# RC_Car_Project_Remote.net
KiCad netlist of a schematic drawn in EasyEDA
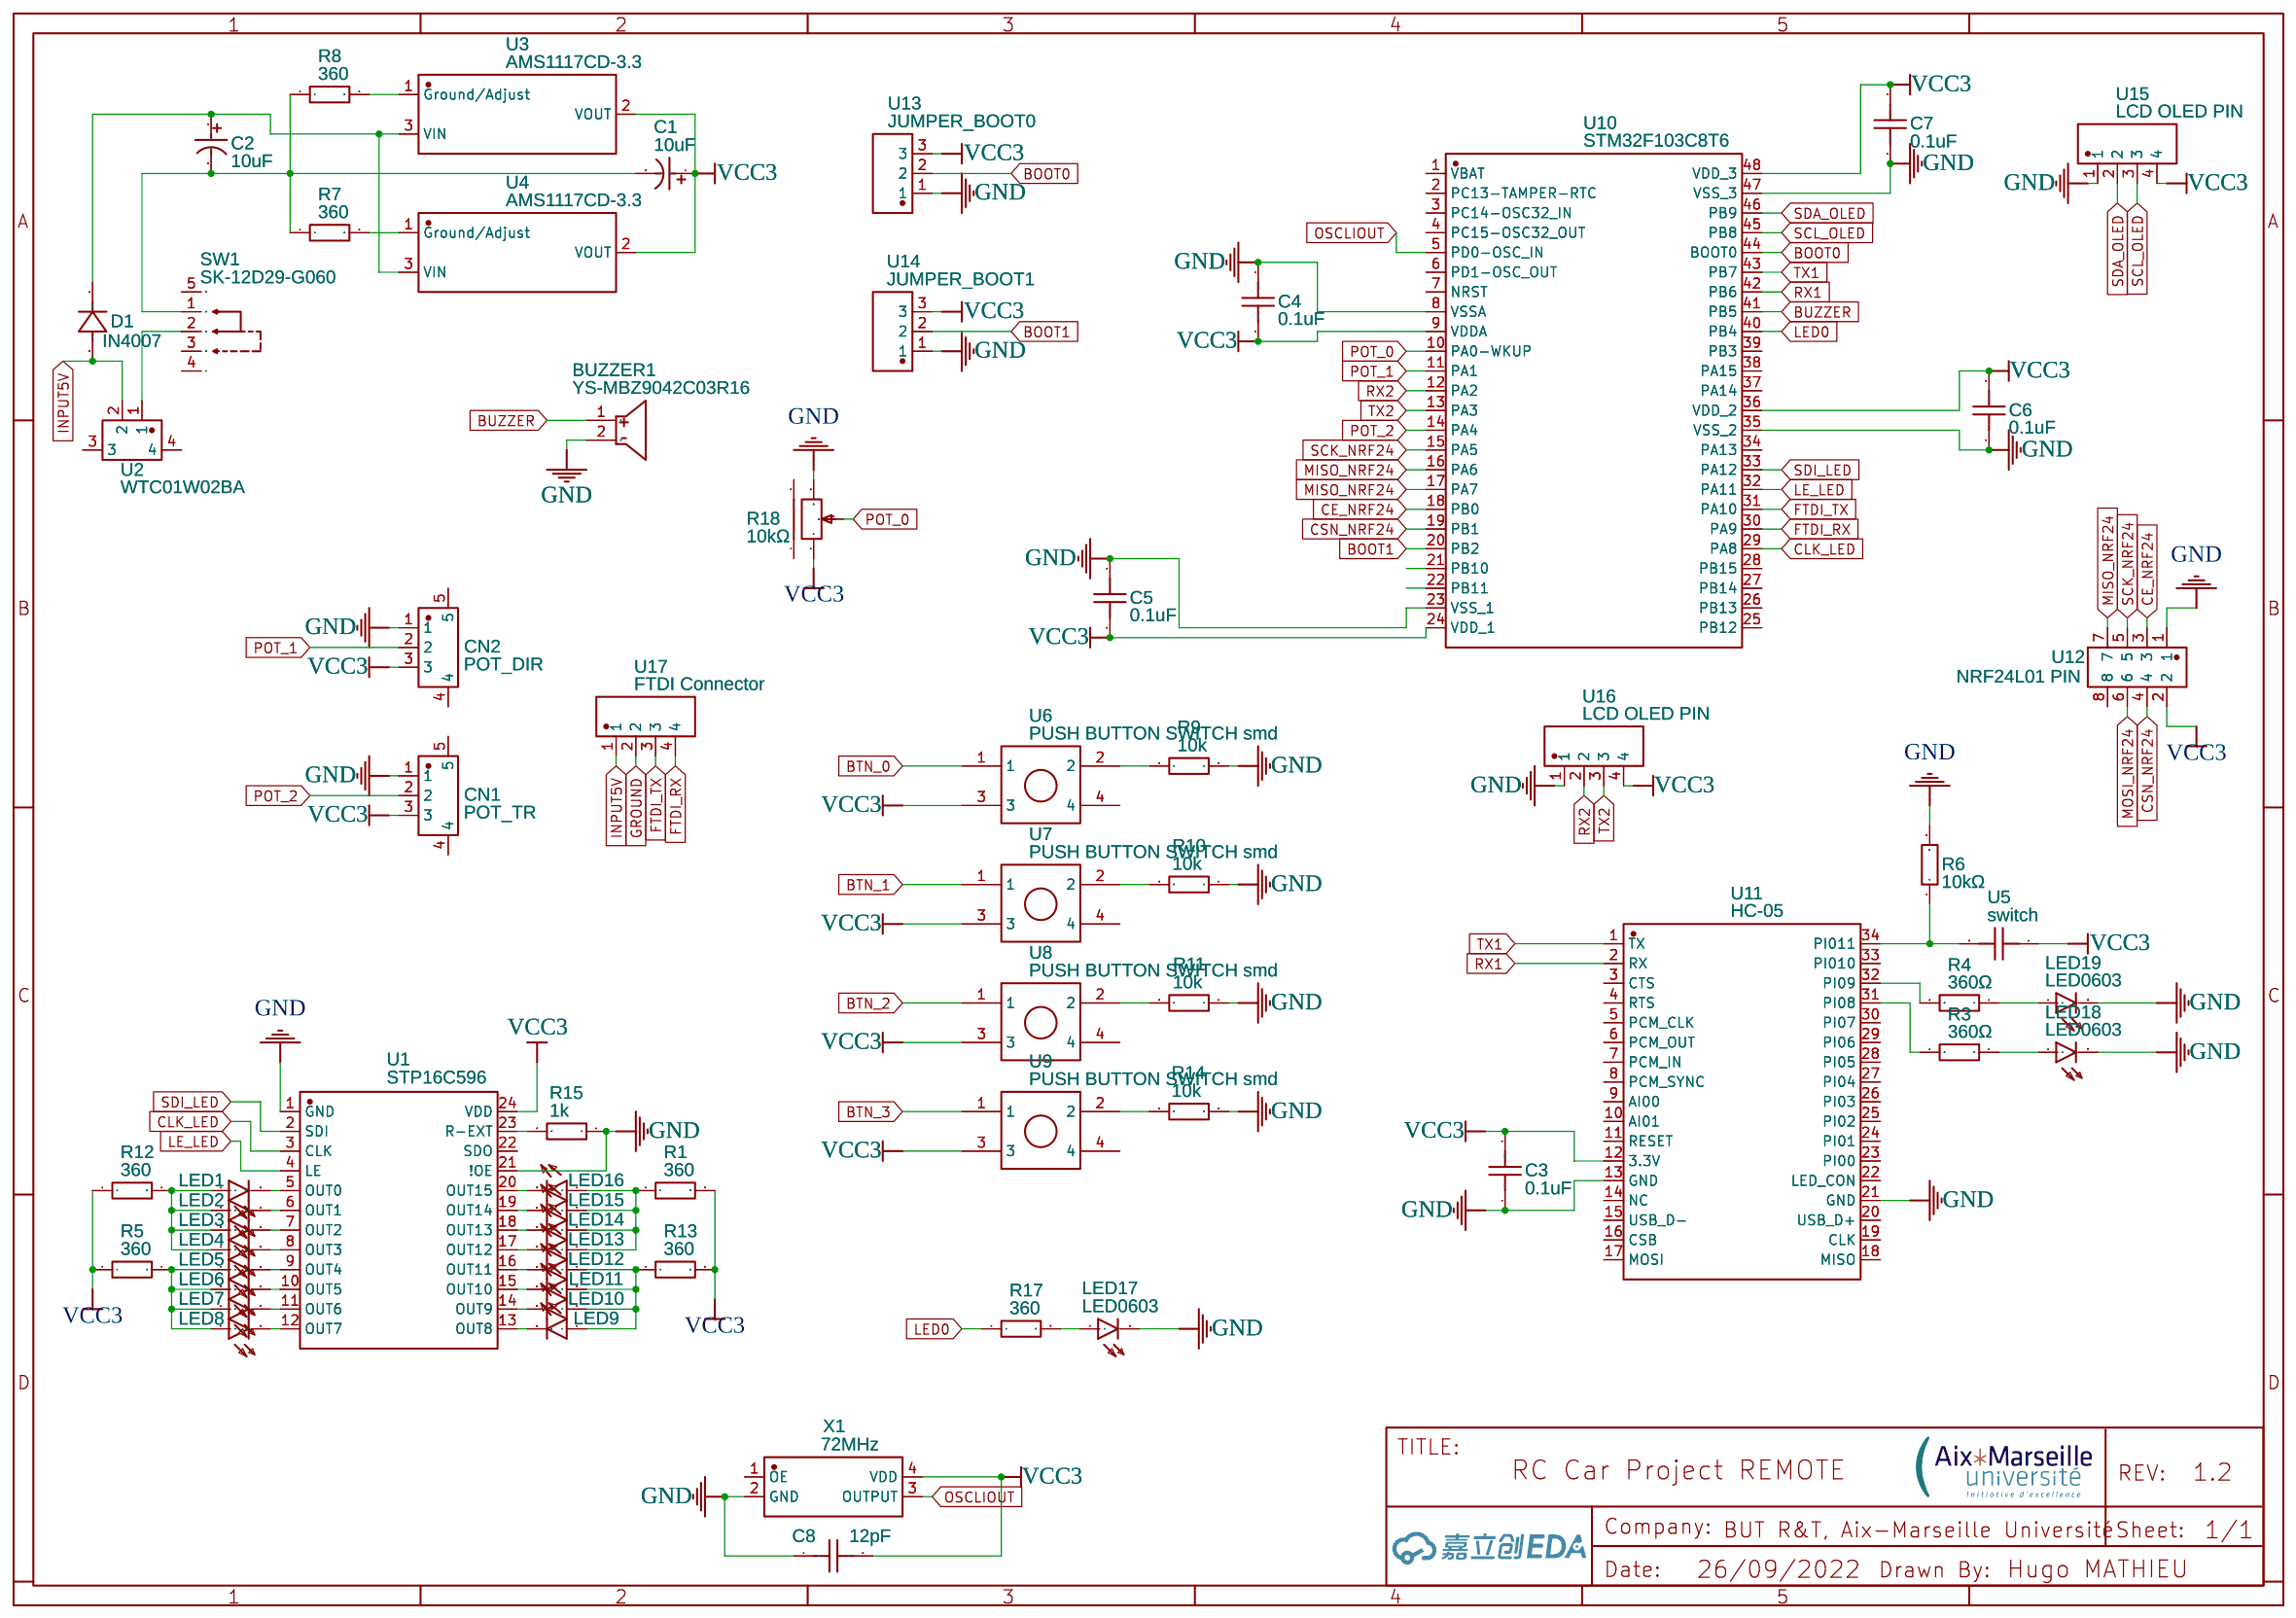
[diagram p0: schematic sheet]

(export (version "E")
  (design (tool "Eeschema 10.0.6"))
  (components
    (comp (ref "BUZZER1")
      (value "YS-MBZ9042C03R16")
      (fields (field (name "BOM_Supplier Part") "C409836"))
      (libsource (lib "") (part "YS-MBZ9042C03R16"))
    )
    (comp (ref "C1")
      (value "10uF")
      (fields
        (field (name "BOM_Manufacturer Part") "RVT1H100M0505")
        (field (name "BOM_Supplier Part") "C72487")
      )
      (libsource (lib "") (part "RVT1H100M0505"))
    )
    (comp (ref "C2")
      (value "10uF")
      (fields
        (field (name "BOM_Manufacturer Part") "RVT1H100M0505")
        (field (name "BOM_Supplier Part") "C72487")
      )
      (libsource (lib "") (part "RVT1H100M0505_1"))
    )
    (comp (ref "C3")
      (value "0.1uF")
      (fields
        (field (name "BOM_Manufacturer Part") "AC0805JRNPO9BN220")
        (field (name "BOM_Supplier Part") "C149614")
      )
      (libsource (lib "") (part "AC0805JRNPO9BN220_1"))
    )
    (comp (ref "C4")
      (value "0.1uF")
      (fields
        (field (name "BOM_Manufacturer Part") "AC0805JRNPO9BN220")
        (field (name "BOM_Supplier Part") "C149614")
      )
      (libsource (lib "") (part "AC0805JRNPO9BN220_2"))
    )
    (comp (ref "C5")
      (value "0.1uF")
      (fields
        (field (name "BOM_Manufacturer Part") "AC0805JRNPO9BN220")
        (field (name "BOM_Supplier Part") "C149614")
      )
      (libsource (lib "") (part "AC0805JRNPO9BN220_2"))
    )
    (comp (ref "C6")
      (value "0.1uF")
      (fields
        (field (name "BOM_Manufacturer Part") "AC0805JRNPO9BN220")
        (field (name "BOM_Supplier Part") "C149614")
      )
      (libsource (lib "") (part "AC0805JRNPO9BN220_1"))
    )
    (comp (ref "C7")
      (value "0.1uF")
      (fields
        (field (name "BOM_Manufacturer Part") "AC0805JRNPO9BN220")
        (field (name "BOM_Supplier Part") "C149614")
      )
      (libsource (lib "") (part "AC0805JRNPO9BN220_1"))
    )
    (comp (ref "C8")
      (value "12pF")
      (fields
        (field (name "BOM_Manufacturer Part") "AC0805JRNPO9BN220")
        (field (name "BOM_Supplier Part") "C149614")
      )
      (libsource (lib "") (part "AC0805JRNPO9BN220"))
    )
    (comp (ref "CN1")
      (value "POT_TR")
      (fields (field (name "BOM_Manufacturer Part") "1.25T-3PWT") (field (name "BOM_Supplier Part") "C22075"))
      (libsource (lib "") (part "1.25T-3PWT"))
    )
    (comp (ref "CN2")
      (value "POT_DIR")
      (fields (field (name "BOM_Manufacturer Part") "1.25T-3PWT") (field (name "BOM_Supplier Part") "C22075"))
      (libsource (lib "") (part "1.25T-3PWT"))
    )
    (comp (ref "D1")
      (value "IN4007")
      (fields (field (name "BOM_Supplier Part") "C9900004719"))
      (libsource (lib "") (part "IN4007"))
    )
    (comp (ref "LED1") (value "LED0603") (libsource (lib "") (part "LED_LEDCHIP-LED0603")))
    (comp (ref "LED2") (value "LED0603") (libsource (lib "") (part "LED_LEDCHIP-LED0603")))
    (comp (ref "LED3") (value "LED0603") (libsource (lib "") (part "LED_LEDCHIP-LED0603")))
    (comp (ref "LED4") (value "LED0603") (libsource (lib "") (part "LED_LEDCHIP-LED0603")))
    (comp (ref "LED5") (value "LED0603") (libsource (lib "") (part "LED_LEDCHIP-LED0603")))
    (comp (ref "LED6") (value "LED0603") (libsource (lib "") (part "LED_LEDCHIP-LED0603")))
    (comp (ref "LED7") (value "LED0603") (libsource (lib "") (part "LED_LEDCHIP-LED0603")))
    (comp (ref "LED8") (value "LED0603") (libsource (lib "") (part "LED_LEDCHIP-LED0603")))
    (comp (ref "LED9") (value "LED0603") (libsource (lib "") (part "LED_LEDCHIP-LED0603_1")))
    (comp (ref "LED10") (value "LED0603") (libsource (lib "") (part "LED_LEDCHIP-LED0603_1")))
    (comp (ref "LED11") (value "LED0603") (libsource (lib "") (part "LED_LEDCHIP-LED0603_1")))
    (comp (ref "LED12") (value "LED0603") (libsource (lib "") (part "LED_LEDCHIP-LED0603_1")))
    (comp (ref "LED13") (value "LED0603") (libsource (lib "") (part "LED_LEDCHIP-LED0603_1")))
    (comp (ref "LED14") (value "LED0603") (libsource (lib "") (part "LED_LEDCHIP-LED0603_1")))
    (comp (ref "LED15") (value "LED0603") (libsource (lib "") (part "LED_LEDCHIP-LED0603_1")))
    (comp (ref "LED16") (value "LED0603") (libsource (lib "") (part "LED_LEDCHIP-LED0603_1")))
    (comp (ref "LED17") (value "LED0603") (libsource (lib "") (part "LED_LEDCHIP-LED0603")))
    (comp (ref "LED18") (value "LED0603") (libsource (lib "") (part "LED_LEDCHIP-LED0603")))
    (comp (ref "LED19") (value "LED0603") (libsource (lib "") (part "LED_LEDCHIP-LED0603")))
    (comp (ref "R1")
      (value "360")
      (fields
        (field (name "BOM_Manufacturer Part") "RC0805FR-07100RL")
        (field (name "BOM_Supplier Part") "C105577")
      )
      (libsource (lib "") (part "RC0805FR-07100RL"))
    )
    (comp (ref "R3")
      (value "360Ω")
      (fields
        (field (name "BOM_Manufacturer Part") "1206W4F1002T5E")
        (field (name "BOM_Supplier Part") "C17902")
      )
      (libsource (lib "") (part "1206W4F1002T5E"))
    )
    (comp (ref "R4")
      (value "360Ω")
      (fields
        (field (name "BOM_Manufacturer Part") "1206W4F1002T5E")
        (field (name "BOM_Supplier Part") "C17902")
      )
      (libsource (lib "") (part "1206W4F1002T5E"))
    )
    (comp (ref "R5")
      (value "360")
      (fields
        (field (name "BOM_Manufacturer Part") "RC0805FR-07100RL")
        (field (name "BOM_Supplier Part") "C105577")
      )
      (libsource (lib "") (part "RC0805FR-07100RL"))
    )
    (comp (ref "R6")
      (value "10kΩ")
      (fields
        (field (name "BOM_Manufacturer Part") "1206W4F1002T5E")
        (field (name "BOM_Supplier Part") "C17902")
      )
      (libsource (lib "") (part "1206W4F1002T5E_1"))
    )
    (comp (ref "R7")
      (value "360")
      (fields
        (field (name "BOM_Manufacturer Part") "RC0805FR-07100RL")
        (field (name "BOM_Supplier Part") "C105577")
      )
      (libsource (lib "") (part "RC0805FR-07100RL"))
    )
    (comp (ref "R8")
      (value "360")
      (fields
        (field (name "BOM_Manufacturer Part") "RC0805FR-07100RL")
        (field (name "BOM_Supplier Part") "C105577")
      )
      (libsource (lib "") (part "RC0805FR-07100RL"))
    )
    (comp (ref "R9")
      (value "10k")
      (fields
        (field (name "BOM_Manufacturer Part") "RC0805FR-07100RL")
        (field (name "BOM_Supplier Part") "C105577")
      )
      (libsource (lib "") (part "RC0805FR-07100RL_1"))
    )
    (comp (ref "R10")
      (value "10k")
      (fields
        (field (name "BOM_Manufacturer Part") "RC0805FR-07100RL")
        (field (name "BOM_Supplier Part") "C105577")
      )
      (libsource (lib "") (part "RC0805FR-07100RL_1"))
    )
    (comp (ref "R11")
      (value "10k")
      (fields
        (field (name "BOM_Manufacturer Part") "RC0805FR-07100RL")
        (field (name "BOM_Supplier Part") "C105577")
      )
      (libsource (lib "") (part "RC0805FR-07100RL_1"))
    )
    (comp (ref "R12")
      (value "360")
      (fields
        (field (name "BOM_Manufacturer Part") "RC0805FR-07100RL")
        (field (name "BOM_Supplier Part") "C105577")
      )
      (libsource (lib "") (part "RC0805FR-07100RL"))
    )
    (comp (ref "R13")
      (value "360")
      (fields
        (field (name "BOM_Manufacturer Part") "RC0805FR-07100RL")
        (field (name "BOM_Supplier Part") "C105577")
      )
      (libsource (lib "") (part "RC0805FR-07100RL"))
    )
    (comp (ref "R14")
      (value "10k")
      (fields
        (field (name "BOM_Manufacturer Part") "RC0805FR-07100RL")
        (field (name "BOM_Supplier Part") "C105577")
      )
      (libsource (lib "") (part "RC0805FR-07100RL_1"))
    )
    (comp (ref "R15")
      (value "1k")
      (fields
        (field (name "BOM_Manufacturer Part") "RC0805FR-07100RL")
        (field (name "BOM_Supplier Part") "C105577")
      )
      (libsource (lib "") (part "RC0805FR-07100RL_1"))
    )
    (comp (ref "R17")
      (value "360")
      (fields
        (field (name "BOM_Manufacturer Part") "RC0805FR-07100RL")
        (field (name "BOM_Supplier Part") "C105577")
      )
      (libsource (lib "") (part "RC0805FR-07100RL"))
    )
    (comp (ref "R18")
      (value "10kΩ")
      (fields
        (field (name "BOM_Manufacturer Part") "RK09K1130AP5")
        (field (name "BOM_Supplier Part") "C470295")
      )
      (libsource (lib "") (part "RK09K1130AP5"))
    )
    (comp (ref "SW1")
      (value "SK-12D29-G060")
      (fields (field (name "BOM_Supplier Part") "C2848877"))
      (libsource (lib "") (part "SK-12D29-G060"))
    )
    (comp (ref "U1")
      (value "STP16C596")
      (fields (field (name "BOM_Supplier Part") "914-2948"))
      (libsource (lib "") (part "STP16C596"))
    )
    (comp (ref "U2")
      (value "WTC01W02BA")
      (fields (field (name "BOM_Supplier Part") "C5120226"))
      (libsource (lib "") (part "WTC01W02BA"))
    )
    (comp (ref "U3")
      (value "AMS1117CD-3.3")
      (fields (field (name "BOM_Supplier Part") "C841796"))
      (libsource (lib "") (part "AMS1117CD-3.3"))
    )
    (comp (ref "U4")
      (value "AMS1117CD-3.3")
      (fields (field (name "BOM_Supplier Part") "C841796"))
      (libsource (lib "") (part "AMS1117CD-3.3"))
    )
    (comp (ref "U5")
      (value "switch")
      (fields
        (field (name "BOM_Manufacturer Part") "0.5pF-C0805")
        (field (name "BOM_Supplier Part") "C9900009443")
      )
      (libsource (lib "") (part "0.5PF-C0805"))
    )
    (comp (ref "U6")
      (value "PUSH BUTTON SWITCH smd")
      (fields (field (name "BOM_Manufacturer Part") "HALO PUSH BUTTON SWITCH"))
      (libsource (lib "") (part "PUSH BUTTON SWITCH smd"))
    )
    (comp (ref "U7")
      (value "PUSH BUTTON SWITCH smd")
      (fields (field (name "BOM_Manufacturer Part") "HALO PUSH BUTTON SWITCH"))
      (libsource (lib "") (part "PUSH BUTTON SWITCH smd"))
    )
    (comp (ref "U8")
      (value "PUSH BUTTON SWITCH smd")
      (fields (field (name "BOM_Manufacturer Part") "HALO PUSH BUTTON SWITCH"))
      (libsource (lib "") (part "PUSH BUTTON SWITCH smd"))
    )
    (comp (ref "U9")
      (value "PUSH BUTTON SWITCH smd")
      (fields (field (name "BOM_Manufacturer Part") "HALO PUSH BUTTON SWITCH"))
      (libsource (lib "") (part "PUSH BUTTON SWITCH smd"))
    )
    (comp (ref "U10")
      (value "STM32F103C8T6")
      (fields (field (name "BOM_Supplier Part") "C8734"))
      (libsource (lib "") (part "STM32F103C8T6"))
    )
    (comp (ref "U11")
      (value "HC-05")
      (fields (field (name "BOM_Supplier Part") "C9900001063"))
      (libsource (lib "") (part "HC-05"))
    )
    (comp (ref "U12")
      (value "NRF24L01 PIN")
      (fields (field (name "BOM_Manufacturer Part") "2.54-2*4") (field (name "BOM_Supplier Part") "C2977588"))
      (libsource (lib "") (part "2.54-2*4"))
    )
    (comp (ref "U13")
      (value "JUMPER_BOOT0")
      (fields
        (field (name "BOM_Manufacturer Part") "2.54*3单排")
        (field (name "BOM_Supplier Part") "C9900016162")
      )
      (libsource (lib "") (part "2.54*3单排"))
    )
    (comp (ref "U14")
      (value "JUMPER_BOOT1")
      (fields
        (field (name "BOM_Manufacturer Part") "2.54*3单排")
        (field (name "BOM_Supplier Part") "C9900016162")
      )
      (libsource (lib "") (part "2.54*3单排"))
    )
    (comp (ref "U15")
      (value "LCD OLED PIN")
      (fields
        (field (name "BOM_Manufacturer Part") "2.54*4单排")
        (field (name "BOM_Supplier Part") "C9900016163")
      )
      (libsource (lib "") (part "2.54*4单排"))
    )
    (comp (ref "U16")
      (value "LCD OLED PIN")
      (fields
        (field (name "BOM_Manufacturer Part") "2.54*4单排")
        (field (name "BOM_Supplier Part") "C9900016163")
      )
      (libsource (lib "") (part "2.54*4单排"))
    )
    (comp (ref "U17")
      (value "FTDI Connector")
      (fields
        (field (name "BOM_Manufacturer Part") "2.54*4单排")
        (field (name "BOM_Supplier Part") "C9900016163")
      )
      (libsource (lib "") (part "2.54*4单排"))
    )
    (comp (ref "X1")
      (value "72MHz")
      (fields
        (field (name "BOM_Manufacturer Part") "S5D13.560000A20F30T")
        (field (name "BOM_Supplier Part") "C387226")
      )
      (libsource (lib "") (part "S5D13.560000A20F30T"))
    )
  )
  (nets
    (net (code "1") (name "BOOT0") (class "Default")
      (node (ref "U10") (pin "44") (pinfunction "BOOT0_44") (pintype "unspecified"))
      (node (ref "U13") (pin "2") (pinfunction "2_2") (pintype "unspecified"))
    )
    (net (code "2") (name "BOOT1") (class "Default")
      (node (ref "U10") (pin "20") (pinfunction "PB2_20") (pintype "unspecified"))
      (node (ref "U14") (pin "2") (pinfunction "2_2") (pintype "unspecified"))
    )
    (net (code "3") (name "BTN_0") (class "Default")
      (node (ref "U6") (pin "1") (pinfunction "1_1") (pintype "unspecified"))
    )
    (net (code "4") (name "BTN_1") (class "Default")
      (node (ref "U7") (pin "1") (pinfunction "1_1") (pintype "unspecified"))
    )
    (net (code "5") (name "BTN_2") (class "Default")
      (node (ref "U8") (pin "1") (pinfunction "1_1") (pintype "unspecified"))
    )
    (net (code "6") (name "BTN_3") (class "Default")
      (node (ref "U9") (pin "1") (pinfunction "1_1") (pintype "unspecified"))
    )
    (net (code "7") (name "BUZZER") (class "Default")
      (node (ref "BUZZER1") (pin "1") (pinfunction "1_1") (pintype "unspecified"))
      (node (ref "U10") (pin "41") (pinfunction "PB5_41") (pintype "unspecified"))
    )
    (net (code "8") (name "CE_NRF24") (class "Default")
      (node (ref "U10") (pin "18") (pinfunction "PB0_18") (pintype "unspecified"))
      (node (ref "U12") (pin "3") (pinfunction "3_3") (pintype "unspecified"))
    )
    (net (code "9") (name "CLK_LED") (class "Default")
      (node (ref "U1") (pin "3") (pinfunction "CLK_3") (pintype "unspecified"))
      (node (ref "U10") (pin "29") (pinfunction "PA8_29") (pintype "unspecified"))
    )
    (net (code "10") (name "CSN_NRF24") (class "Default")
      (node (ref "U10") (pin "19") (pinfunction "PB1_19") (pintype "unspecified"))
      (node (ref "U12") (pin "4") (pinfunction "4_4") (pintype "unspecified"))
    )
    (net (code "11") (name "FTDI_RX") (class "Default")
      (node (ref "U10") (pin "30") (pinfunction "PA9_30") (pintype "unspecified"))
      (node (ref "U17") (pin "4") (pinfunction "4_4") (pintype "unspecified"))
    )
    (net (code "12") (name "FTDI_TX") (class "Default")
      (node (ref "U10") (pin "31") (pinfunction "PA10_31") (pintype "unspecified"))
      (node (ref "U17") (pin "3") (pinfunction "3_3") (pintype "unspecified"))
    )
    (net (code "13") (name "GND") (class "Default")
      (node (ref "BUZZER1") (pin "2") (pinfunction "2_2") (pintype "unspecified"))
      (node (ref "C3") (pin "1") (pinfunction "1_1") (pintype "unspecified"))
      (node (ref "C4") (pin "1") (pinfunction "1_1") (pintype "unspecified"))
      (node (ref "C5") (pin "1") (pinfunction "1_1") (pintype "unspecified"))
      (node (ref "C6") (pin "1") (pinfunction "1_1") (pintype "unspecified"))
      (node (ref "C7") (pin "1") (pinfunction "1_1") (pintype "unspecified"))
      (node (ref "C8") (pin "1") (pinfunction "1_1") (pintype "unspecified"))
      (node (ref "CN1") (pin "1") (pinfunction "1_1") (pintype "unspecified"))
      (node (ref "CN2") (pin "1") (pinfunction "1_1") (pintype "unspecified"))
      (node (ref "LED17") (pin "C") (pinfunction "C_C") (pintype "bidirectional"))
      (node (ref "LED18") (pin "C") (pinfunction "C_C") (pintype "bidirectional"))
      (node (ref "LED19") (pin "C") (pinfunction "C_C") (pintype "bidirectional"))
      (node (ref "R10") (pin "1") (pinfunction "1_1") (pintype "input"))
      (node (ref "R11") (pin "1") (pinfunction "1_1") (pintype "input"))
      (node (ref "R14") (pin "1") (pinfunction "1_1") (pintype "input"))
      (node (ref "R15") (pin "1") (pinfunction "1_1") (pintype "input"))
      (node (ref "R18") (pin "3") (pinfunction "3_3") (pintype "input"))
      (node (ref "R6") (pin "2") (pinfunction "2_2") (pintype "input"))
      (node (ref "R9") (pin "1") (pinfunction "1_1") (pintype "input"))
      (node (ref "U1") (pin "1") (pinfunction "GND_1") (pintype "unspecified"))
      (node (ref "U1") (pin "21") (pinfunction "!OE_21") (pintype "unspecified"))
      (node (ref "U10") (pin "23") (pinfunction "VSS_1_23") (pintype "unspecified"))
      (node (ref "U10") (pin "35") (pinfunction "VSS_2_35") (pintype "unspecified"))
      (node (ref "U10") (pin "47") (pinfunction "VSS_3_47") (pintype "unspecified"))
      (node (ref "U10") (pin "8") (pinfunction "VSSA_8") (pintype "unspecified"))
      (node (ref "U11") (pin "13") (pinfunction "GND_13") (pintype "unspecified"))
      (node (ref "U11") (pin "21") (pinfunction "GND_21") (pintype "unspecified"))
      (node (ref "U12") (pin "1") (pinfunction "1_1") (pintype "unspecified"))
      (node (ref "U13") (pin "1") (pinfunction "1_1") (pintype "unspecified"))
      (node (ref "U14") (pin "1") (pinfunction "1_1") (pintype "unspecified"))
      (node (ref "U15") (pin "1") (pinfunction "1_1") (pintype "unspecified"))
      (node (ref "U16") (pin "1") (pinfunction "1_1") (pintype "unspecified"))
      (node (ref "X1") (pin "2") (pinfunction "GND_2") (pintype "unspecified"))
    )
    (net (code "14") (name "GROUND") (class "Default")
      (node (ref "U17") (pin "2") (pinfunction "2_2") (pintype "unspecified"))
    )
    (net (code "15") (name "INPUT5V") (class "Default")
      (node (ref "D1") (pin "2") (pinfunction "A_2") (pintype "unspecified"))
      (node (ref "U17") (pin "1") (pinfunction "1_1") (pintype "unspecified"))
      (node (ref "U2") (pin "2") (pinfunction "2_2") (pintype "unspecified"))
    )
    (net (code "16") (name "LED0") (class "Default")
      (node (ref "R17") (pin "1") (pinfunction "1_1") (pintype "input"))
      (node (ref "U10") (pin "40") (pinfunction "PB4_40") (pintype "unspecified"))
    )
    (net (code "17") (name "LE_LED") (class "Default")
      (node (ref "U1") (pin "4") (pinfunction "LE_4") (pintype "unspecified"))
      (node (ref "U10") (pin "32") (pinfunction "PA11_32") (pintype "unspecified"))
    )
    (net (code "18") (name "MISO_NRF24") (class "Default")
      (node (ref "U10") (pin "16") (pinfunction "PA6_16") (pintype "unspecified"))
      (node (ref "U10") (pin "17") (pinfunction "PA7_17") (pintype "unspecified"))
      (node (ref "U12") (pin "7") (pinfunction "7_7") (pintype "unspecified"))
    )
    (net (code "19") (name "MOSI_NRF24") (class "Default")
      (node (ref "U12") (pin "6") (pinfunction "6_6") (pintype "unspecified"))
    )
    (net (code "20") (name "Net-(C1-Pad2)") (class "Default")
      (node (ref "C1") (pin "2") (pinfunction "2_2") (pintype "input"))
      (node (ref "C2") (pin "2") (pinfunction "2_2") (pintype "input"))
      (node (ref "R7") (pin "1") (pinfunction "1_1") (pintype "input"))
      (node (ref "R8") (pin "1") (pinfunction "1_1") (pintype "input"))
      (node (ref "SW1") (pin "1") (pinfunction "1_1") (pintype "unspecified"))
    )
    (net (code "21") (name "Net-(D1-K)") (class "Default")
      (node (ref "C2") (pin "1") (pinfunction "1_1") (pintype "input"))
      (node (ref "D1") (pin "1") (pinfunction "K_1") (pintype "unspecified"))
      (node (ref "U3") (pin "3") (pinfunction "VIN_3") (pintype "unspecified"))
      (node (ref "U4") (pin "3") (pinfunction "VIN_3") (pintype "unspecified"))
    )
    (net (code "22") (name "Net-(LED1-PadA)") (class "Default")
      (node (ref "LED1") (pin "A") (pinfunction "A_A") (pintype "bidirectional"))
      (node (ref "LED2") (pin "A") (pinfunction "A_A") (pintype "bidirectional"))
      (node (ref "LED3") (pin "A") (pinfunction "A_A") (pintype "bidirectional"))
      (node (ref "LED4") (pin "A") (pinfunction "A_A") (pintype "bidirectional"))
      (node (ref "R12") (pin "2") (pinfunction "2_2") (pintype "input"))
    )
    (net (code "23") (name "Net-(LED5-PadA)") (class "Default")
      (node (ref "LED5") (pin "A") (pinfunction "A_A") (pintype "bidirectional"))
      (node (ref "LED6") (pin "A") (pinfunction "A_A") (pintype "bidirectional"))
      (node (ref "LED7") (pin "A") (pinfunction "A_A") (pintype "bidirectional"))
      (node (ref "LED8") (pin "A") (pinfunction "A_A") (pintype "bidirectional"))
      (node (ref "R5") (pin "2") (pinfunction "2_2") (pintype "input"))
    )
    (net (code "24") (name "Net-(LED10-PadA)") (class "Default")
      (node (ref "LED10") (pin "A") (pinfunction "A_A") (pintype "bidirectional"))
      (node (ref "LED11") (pin "A") (pinfunction "A_A") (pintype "bidirectional"))
      (node (ref "LED12") (pin "A") (pinfunction "A_A") (pintype "bidirectional"))
      (node (ref "LED9") (pin "A") (pinfunction "A_A") (pintype "bidirectional"))
      (node (ref "R13") (pin "1") (pinfunction "1_1") (pintype "input"))
    )
    (net (code "25") (name "Net-(LED13-PadA)") (class "Default")
      (node (ref "LED13") (pin "A") (pinfunction "A_A") (pintype "bidirectional"))
      (node (ref "LED14") (pin "A") (pinfunction "A_A") (pintype "bidirectional"))
      (node (ref "LED15") (pin "A") (pinfunction "A_A") (pintype "bidirectional"))
      (node (ref "LED16") (pin "A") (pinfunction "A_A") (pintype "bidirectional"))
      (node (ref "R1") (pin "1") (pinfunction "1_1") (pintype "input"))
    )
    (net (code "26") (name "Net-(LED17-PadA)") (class "Default")
      (node (ref "LED17") (pin "A") (pinfunction "A_A") (pintype "bidirectional"))
      (node (ref "R17") (pin "2") (pinfunction "2_2") (pintype "input"))
    )
    (net (code "27") (name "Net-(LED18-PadA)") (class "Default")
      (node (ref "LED18") (pin "A") (pinfunction "A_A") (pintype "bidirectional"))
      (node (ref "R3") (pin "1") (pinfunction "1_1") (pintype "input"))
    )
    (net (code "28") (name "Net-(LED19-PadA)") (class "Default")
      (node (ref "LED19") (pin "A") (pinfunction "A_A") (pintype "bidirectional"))
      (node (ref "R4") (pin "1") (pinfunction "1_1") (pintype "input"))
    )
    (net (code "29") (name "Net-(R9-Pad2)") (class "Default")
      (node (ref "R9") (pin "2") (pinfunction "2_2") (pintype "input"))
      (node (ref "U6") (pin "2") (pinfunction "2_2") (pintype "unspecified"))
    )
    (net (code "30") (name "Net-(R10-Pad2)") (class "Default")
      (node (ref "R10") (pin "2") (pinfunction "2_2") (pintype "input"))
      (node (ref "U7") (pin "2") (pinfunction "2_2") (pintype "unspecified"))
    )
    (net (code "31") (name "Net-(R11-Pad2)") (class "Default")
      (node (ref "R11") (pin "2") (pinfunction "2_2") (pintype "input"))
      (node (ref "U8") (pin "2") (pinfunction "2_2") (pintype "unspecified"))
    )
    (net (code "32") (name "Net-(R14-Pad2)") (class "Default")
      (node (ref "R14") (pin "2") (pinfunction "2_2") (pintype "input"))
      (node (ref "U9") (pin "2") (pinfunction "2_2") (pintype "unspecified"))
    )
    (net (code "33") (name "Net-(SW1-Pad2)") (class "Default")
      (node (ref "SW1") (pin "2") (pinfunction "2_2") (pintype "unspecified"))
      (node (ref "U2") (pin "1") (pinfunction "1_1") (pintype "unspecified"))
    )
    (net (code "34") (name "Net-(U1-OUT0)") (class "Default")
      (node (ref "LED1") (pin "C") (pinfunction "C_C") (pintype "bidirectional"))
      (node (ref "U1") (pin "5") (pinfunction "OUT0_5") (pintype "unspecified"))
    )
    (net (code "35") (name "Net-(U1-OUT1)") (class "Default")
      (node (ref "LED2") (pin "C") (pinfunction "C_C") (pintype "bidirectional"))
      (node (ref "U1") (pin "6") (pinfunction "OUT1_6") (pintype "unspecified"))
    )
    (net (code "36") (name "Net-(U1-OUT2)") (class "Default")
      (node (ref "LED3") (pin "C") (pinfunction "C_C") (pintype "bidirectional"))
      (node (ref "U1") (pin "7") (pinfunction "OUT2_7") (pintype "unspecified"))
    )
    (net (code "37") (name "Net-(U1-OUT3)") (class "Default")
      (node (ref "LED4") (pin "C") (pinfunction "C_C") (pintype "bidirectional"))
      (node (ref "U1") (pin "8") (pinfunction "OUT3_8") (pintype "unspecified"))
    )
    (net (code "38") (name "Net-(U1-OUT4)") (class "Default")
      (node (ref "LED5") (pin "C") (pinfunction "C_C") (pintype "bidirectional"))
      (node (ref "U1") (pin "9") (pinfunction "OUT4_9") (pintype "unspecified"))
    )
    (net (code "39") (name "Net-(U1-OUT5)") (class "Default")
      (node (ref "LED6") (pin "C") (pinfunction "C_C") (pintype "bidirectional"))
      (node (ref "U1") (pin "10") (pinfunction "OUT5_10") (pintype "unspecified"))
    )
    (net (code "40") (name "Net-(U1-OUT6)") (class "Default")
      (node (ref "LED7") (pin "C") (pinfunction "C_C") (pintype "bidirectional"))
      (node (ref "U1") (pin "11") (pinfunction "OUT6_11") (pintype "unspecified"))
    )
    (net (code "41") (name "Net-(U1-OUT7)") (class "Default")
      (node (ref "LED8") (pin "C") (pinfunction "C_C") (pintype "bidirectional"))
      (node (ref "U1") (pin "12") (pinfunction "OUT7_12") (pintype "unspecified"))
    )
    (net (code "42") (name "Net-(U1-OUT8)") (class "Default")
      (node (ref "LED9") (pin "C") (pinfunction "C_C") (pintype "bidirectional"))
      (node (ref "U1") (pin "13") (pinfunction "OUT8_13") (pintype "unspecified"))
    )
    (net (code "43") (name "Net-(U1-OUT9)") (class "Default")
      (node (ref "LED10") (pin "C") (pinfunction "C_C") (pintype "bidirectional"))
      (node (ref "U1") (pin "14") (pinfunction "OUT9_14") (pintype "unspecified"))
    )
    (net (code "44") (name "Net-(U1-OUT10)") (class "Default")
      (node (ref "LED11") (pin "C") (pinfunction "C_C") (pintype "bidirectional"))
      (node (ref "U1") (pin "15") (pinfunction "OUT10_15") (pintype "unspecified"))
    )
    (net (code "45") (name "Net-(U1-OUT11)") (class "Default")
      (node (ref "LED12") (pin "C") (pinfunction "C_C") (pintype "bidirectional"))
      (node (ref "U1") (pin "16") (pinfunction "OUT11_16") (pintype "unspecified"))
    )
    (net (code "46") (name "Net-(U1-OUT12)") (class "Default")
      (node (ref "LED13") (pin "C") (pinfunction "C_C") (pintype "bidirectional"))
      (node (ref "U1") (pin "17") (pinfunction "OUT12_17") (pintype "unspecified"))
    )
    (net (code "47") (name "Net-(U1-OUT13)") (class "Default")
      (node (ref "LED14") (pin "C") (pinfunction "C_C") (pintype "bidirectional"))
      (node (ref "U1") (pin "18") (pinfunction "OUT13_18") (pintype "unspecified"))
    )
    (net (code "48") (name "Net-(U1-OUT14)") (class "Default")
      (node (ref "LED15") (pin "C") (pinfunction "C_C") (pintype "bidirectional"))
      (node (ref "U1") (pin "19") (pinfunction "OUT14_19") (pintype "unspecified"))
    )
    (net (code "49") (name "Net-(U1-OUT15)") (class "Default")
      (node (ref "LED16") (pin "C") (pinfunction "C_C") (pintype "bidirectional"))
      (node (ref "U1") (pin "20") (pinfunction "OUT15_20") (pintype "unspecified"))
    )
    (net (code "50") (name "Net-(U1-R-EXT)") (class "Default")
      (node (ref "R15") (pin "2") (pinfunction "2_2") (pintype "input"))
      (node (ref "U1") (pin "23") (pinfunction "R-EXT_23") (pintype "unspecified"))
    )
    (net (code "51") (name "Net-(U3-Ground{slash}Adjust)") (class "Default")
      (node (ref "R8") (pin "2") (pinfunction "2_2") (pintype "input"))
      (node (ref "U3") (pin "1") (pinfunction "Ground/Adjust_1") (pintype "unspecified"))
    )
    (net (code "52") (name "Net-(U4-Ground{slash}Adjust)") (class "Default")
      (node (ref "R7") (pin "2") (pinfunction "2_2") (pintype "input"))
      (node (ref "U4") (pin "1") (pinfunction "Ground/Adjust_1") (pintype "unspecified"))
    )
    (net (code "53") (name "Net-(U11-PI08)") (class "Default")
      (node (ref "R3") (pin "2") (pinfunction "2_2") (pintype "input"))
      (node (ref "U11") (pin "31") (pinfunction "PI08_31") (pintype "unspecified"))
    )
    (net (code "54") (name "Net-(U11-PI09)") (class "Default")
      (node (ref "R4") (pin "2") (pinfunction "2_2") (pintype "input"))
      (node (ref "U11") (pin "32") (pinfunction "PI09_32") (pintype "unspecified"))
    )
    (net (code "55") (name "Net-(U11-PI011)") (class "Default")
      (node (ref "R6") (pin "1") (pinfunction "1_1") (pintype "input"))
      (node (ref "U11") (pin "34") (pinfunction "PI011_34") (pintype "unspecified"))
      (node (ref "U5") (pin "2") (pinfunction "2_2") (pintype "unspecified"))
    )
    (net (code "56") (name "OSCLIOUT") (class "Default")
      (node (ref "U10") (pin "5") (pinfunction "PD0-OSC_IN_5") (pintype "unspecified"))
      (node (ref "X1") (pin "3") (pinfunction "OUTPUT_3") (pintype "unspecified"))
    )
    (net (code "57") (name "POT_0") (class "Default")
      (node (ref "R18") (pin "2") (pinfunction "2_2") (pintype "input"))
      (node (ref "U10") (pin "10") (pinfunction "PA0-WKUP_10") (pintype "unspecified"))
    )
    (net (code "58") (name "POT_1") (class "Default")
      (node (ref "CN2") (pin "2") (pinfunction "2_2") (pintype "unspecified"))
      (node (ref "U10") (pin "11") (pinfunction "PA1_11") (pintype "unspecified"))
    )
    (net (code "59") (name "POT_2") (class "Default")
      (node (ref "CN1") (pin "2") (pinfunction "2_2") (pintype "unspecified"))
      (node (ref "U10") (pin "14") (pinfunction "PA4_14") (pintype "unspecified"))
    )
    (net (code "60") (name "RX1") (class "Default")
      (node (ref "U10") (pin "42") (pinfunction "PB6_42") (pintype "unspecified"))
      (node (ref "U11") (pin "2") (pinfunction "RX_2") (pintype "unspecified"))
    )
    (net (code "61") (name "RX2") (class "Default")
      (node (ref "U10") (pin "12") (pinfunction "PA2_12") (pintype "unspecified"))
      (node (ref "U16") (pin "2") (pinfunction "2_2") (pintype "unspecified"))
    )
    (net (code "62") (name "SCK_NRF24") (class "Default")
      (node (ref "U10") (pin "15") (pinfunction "PA5_15") (pintype "unspecified"))
      (node (ref "U12") (pin "5") (pinfunction "5_5") (pintype "unspecified"))
    )
    (net (code "63") (name "SCL_OLED") (class "Default")
      (node (ref "U10") (pin "45") (pinfunction "PB8_45") (pintype "unspecified"))
      (node (ref "U15") (pin "3") (pinfunction "3_3") (pintype "unspecified"))
    )
    (net (code "64") (name "SDA_OLED") (class "Default")
      (node (ref "U10") (pin "46") (pinfunction "PB9_46") (pintype "unspecified"))
      (node (ref "U15") (pin "2") (pinfunction "2_2") (pintype "unspecified"))
    )
    (net (code "65") (name "SDI_LED") (class "Default")
      (node (ref "U1") (pin "2") (pinfunction "SDI_2") (pintype "unspecified"))
      (node (ref "U10") (pin "33") (pinfunction "PA12_33") (pintype "unspecified"))
    )
    (net (code "66") (name "TX1") (class "Default")
      (node (ref "U10") (pin "43") (pinfunction "PB7_43") (pintype "unspecified"))
      (node (ref "U11") (pin "1") (pinfunction "TX_1") (pintype "unspecified"))
    )
    (net (code "67") (name "TX2") (class "Default")
      (node (ref "U10") (pin "13") (pinfunction "PA3_13") (pintype "unspecified"))
      (node (ref "U16") (pin "3") (pinfunction "3_3") (pintype "unspecified"))
    )
    (net (code "68") (name "VCC3") (class "Default")
      (node (ref "C1") (pin "1") (pinfunction "1_1") (pintype "input"))
      (node (ref "C3") (pin "2") (pinfunction "2_2") (pintype "unspecified"))
      (node (ref "C4") (pin "2") (pinfunction "2_2") (pintype "unspecified"))
      (node (ref "C5") (pin "2") (pinfunction "2_2") (pintype "unspecified"))
      (node (ref "C6") (pin "2") (pinfunction "2_2") (pintype "unspecified"))
      (node (ref "C7") (pin "2") (pinfunction "2_2") (pintype "unspecified"))
      (node (ref "C8") (pin "2") (pinfunction "2_2") (pintype "unspecified"))
      (node (ref "CN1") (pin "3") (pinfunction "3_3") (pintype "unspecified"))
      (node (ref "CN2") (pin "3") (pinfunction "3_3") (pintype "unspecified"))
      (node (ref "R1") (pin "2") (pinfunction "2_2") (pintype "input"))
      (node (ref "R12") (pin "1") (pinfunction "1_1") (pintype "input"))
      (node (ref "R13") (pin "2") (pinfunction "2_2") (pintype "input"))
      (node (ref "R18") (pin "1") (pinfunction "1_1") (pintype "input"))
      (node (ref "R5") (pin "1") (pinfunction "1_1") (pintype "input"))
      (node (ref "U1") (pin "24") (pinfunction "VDD_24") (pintype "unspecified"))
      (node (ref "U10") (pin "24") (pinfunction "VDD_1_24") (pintype "unspecified"))
      (node (ref "U10") (pin "36") (pinfunction "VDD_2_36") (pintype "unspecified"))
      (node (ref "U10") (pin "48") (pinfunction "VDD_3_48") (pintype "unspecified"))
      (node (ref "U10") (pin "9") (pinfunction "VDDA_9") (pintype "unspecified"))
      (node (ref "U11") (pin "12") (pinfunction "3.3V_12") (pintype "unspecified"))
      (node (ref "U12") (pin "2") (pinfunction "2_2") (pintype "unspecified"))
      (node (ref "U13") (pin "3") (pinfunction "3_3") (pintype "unspecified"))
      (node (ref "U14") (pin "3") (pinfunction "3_3") (pintype "unspecified"))
      (node (ref "U15") (pin "4") (pinfunction "4_4") (pintype "unspecified"))
      (node (ref "U16") (pin "4") (pinfunction "4_4") (pintype "unspecified"))
      (node (ref "U3") (pin "2") (pinfunction "VOUT_2") (pintype "unspecified"))
      (node (ref "U4") (pin "2") (pinfunction "VOUT_2") (pintype "unspecified"))
      (node (ref "U5") (pin "1") (pinfunction "1_1") (pintype "unspecified"))
      (node (ref "U6") (pin "3") (pinfunction "3_3") (pintype "unspecified"))
      (node (ref "U7") (pin "3") (pinfunction "3_3") (pintype "unspecified"))
      (node (ref "U8") (pin "3") (pinfunction "3_3") (pintype "unspecified"))
      (node (ref "U9") (pin "3") (pinfunction "3_3") (pintype "unspecified"))
      (node (ref "X1") (pin "4") (pinfunction "VDD_4") (pintype "unspecified"))
    )
    (net (code "69") (name "unconnected-(CN1-Pad4)") (class "Default")
      (node (ref "CN1") (pin "4") (pinfunction "4_4") (pintype "unspecified"))
    )
    (net (code "70") (name "unconnected-(CN1-Pad5)") (class "Default")
      (node (ref "CN1") (pin "5") (pinfunction "5_5") (pintype "unspecified"))
    )
    (net (code "71") (name "unconnected-(CN2-Pad4)") (class "Default")
      (node (ref "CN2") (pin "4") (pinfunction "4_4") (pintype "unspecified"))
    )
    (net (code "72") (name "unconnected-(CN2-Pad5)") (class "Default")
      (node (ref "CN2") (pin "5") (pinfunction "5_5") (pintype "unspecified"))
    )
    (net (code "73") (name "unconnected-(R18-Pad4)") (class "Default")
      (node (ref "R18") (pin "4") (pinfunction "4_4") (pintype "input"))
    )
    (net (code "74") (name "unconnected-(R18-Pad5)") (class "Default")
      (node (ref "R18") (pin "5") (pinfunction "5_5") (pintype "input"))
    )
    (net (code "75") (name "unconnected-(SW1-Pad3)") (class "Default")
      (node (ref "SW1") (pin "3") (pinfunction "3_3") (pintype "unspecified"))
    )
    (net (code "76") (name "unconnected-(SW1-Pad4)") (class "Default")
      (node (ref "SW1") (pin "4") (pinfunction "4_4") (pintype "unspecified"))
    )
    (net (code "77") (name "unconnected-(SW1-Pad5)") (class "Default")
      (node (ref "SW1") (pin "5") (pinfunction "5_5") (pintype "unspecified"))
    )
    (net (code "78") (name "unconnected-(U1-SDO-Pad22)") (class "Default")
      (node (ref "U1") (pin "22") (pinfunction "SDO_22") (pintype "unspecified"))
    )
    (net (code "79") (name "unconnected-(U2-Pad3)") (class "Default")
      (node (ref "U2") (pin "3") (pinfunction "3_3") (pintype "unspecified"))
    )
    (net (code "80") (name "unconnected-(U2-Pad4)") (class "Default")
      (node (ref "U2") (pin "4") (pinfunction "4_4") (pintype "unspecified"))
    )
    (net (code "81") (name "unconnected-(U6-Pad4)") (class "Default")
      (node (ref "U6") (pin "4") (pinfunction "4_4") (pintype "unspecified"))
    )
    (net (code "82") (name "unconnected-(U7-Pad4)") (class "Default")
      (node (ref "U7") (pin "4") (pinfunction "4_4") (pintype "unspecified"))
    )
    (net (code "83") (name "unconnected-(U8-Pad4)") (class "Default")
      (node (ref "U8") (pin "4") (pinfunction "4_4") (pintype "unspecified"))
    )
    (net (code "84") (name "unconnected-(U9-Pad4)") (class "Default")
      (node (ref "U9") (pin "4") (pinfunction "4_4") (pintype "unspecified"))
    )
    (net (code "85") (name "unconnected-(U10-NRST-Pad7)") (class "Default")
      (node (ref "U10") (pin "7") (pinfunction "NRST_7") (pintype "unspecified"))
    )
    (net (code "86") (name "unconnected-(U10-PA13-Pad34)") (class "Default")
      (node (ref "U10") (pin "34") (pinfunction "PA13_34") (pintype "unspecified"))
    )
    (net (code "87") (name "unconnected-(U10-PA14-Pad37)") (class "Default")
      (node (ref "U10") (pin "37") (pinfunction "PA14_37") (pintype "unspecified"))
    )
    (net (code "88") (name "unconnected-(U10-PA15-Pad38)") (class "Default")
      (node (ref "U10") (pin "38") (pinfunction "PA15_38") (pintype "unspecified"))
    )
    (net (code "89") (name "unconnected-(U10-PB3-Pad39)") (class "Default")
      (node (ref "U10") (pin "39") (pinfunction "PB3_39") (pintype "unspecified"))
    )
    (net (code "90") (name "unconnected-(U10-PB10-Pad21)") (class "Default")
      (node (ref "U10") (pin "21") (pinfunction "PB10_21") (pintype "unspecified"))
    )
    (net (code "91") (name "unconnected-(U10-PB11-Pad22)") (class "Default")
      (node (ref "U10") (pin "22") (pinfunction "PB11_22") (pintype "unspecified"))
    )
    (net (code "92") (name "unconnected-(U10-PB12-Pad25)") (class "Default")
      (node (ref "U10") (pin "25") (pinfunction "PB12_25") (pintype "unspecified"))
    )
    (net (code "93") (name "unconnected-(U10-PB13-Pad26)") (class "Default")
      (node (ref "U10") (pin "26") (pinfunction "PB13_26") (pintype "unspecified"))
    )
    (net (code "94") (name "unconnected-(U10-PB14-Pad27)") (class "Default")
      (node (ref "U10") (pin "27") (pinfunction "PB14_27") (pintype "unspecified"))
    )
    (net (code "95") (name "unconnected-(U10-PB15-Pad28)") (class "Default")
      (node (ref "U10") (pin "28") (pinfunction "PB15_28") (pintype "unspecified"))
    )
    (net (code "96") (name "unconnected-(U10-PC13-TAMPER-RTC-Pad2)") (class "Default")
      (node (ref "U10") (pin "2") (pinfunction "PC13-TAMPER-RTC_2") (pintype "unspecified"))
    )
    (net (code "97") (name "unconnected-(U10-PC14-OSC32_IN-Pad3)") (class "Default")
      (node (ref "U10") (pin "3") (pinfunction "PC14-OSC32_IN_3") (pintype "unspecified"))
    )
    (net (code "98") (name "unconnected-(U10-PC15-OSC32_OUT-Pad4)") (class "Default")
      (node (ref "U10") (pin "4") (pinfunction "PC15-OSC32_OUT_4") (pintype "unspecified"))
    )
    (net (code "99") (name "unconnected-(U10-PD1-OSC_OUT-Pad6)") (class "Default")
      (node (ref "U10") (pin "6") (pinfunction "PD1-OSC_OUT_6") (pintype "unspecified"))
    )
    (net (code "100") (name "unconnected-(U10-VBAT-Pad1)") (class "Default")
      (node (ref "U10") (pin "1") (pinfunction "VBAT_1") (pintype "unspecified"))
    )
    (net (code "101") (name "unconnected-(U11-AI00-Pad9)") (class "Default")
      (node (ref "U11") (pin "9") (pinfunction "AI00_9") (pintype "unspecified"))
    )
    (net (code "102") (name "unconnected-(U11-AI01-Pad10)") (class "Default")
      (node (ref "U11") (pin "10") (pinfunction "AI01_10") (pintype "unspecified"))
    )
    (net (code "103") (name "unconnected-(U11-CLK-Pad19)") (class "Default")
      (node (ref "U11") (pin "19") (pinfunction "CLK_19") (pintype "unspecified"))
    )
    (net (code "104") (name "unconnected-(U11-CSB-Pad16)") (class "Default")
      (node (ref "U11") (pin "16") (pinfunction "CSB_16") (pintype "unspecified"))
    )
    (net (code "105") (name "unconnected-(U11-CTS-Pad3)") (class "Default")
      (node (ref "U11") (pin "3") (pinfunction "CTS_3") (pintype "unspecified"))
    )
    (net (code "106") (name "unconnected-(U11-LED_CON-Pad22)") (class "Default")
      (node (ref "U11") (pin "22") (pinfunction "LED_CON_22") (pintype "unspecified"))
    )
    (net (code "107") (name "unconnected-(U11-MISO-Pad18)") (class "Default")
      (node (ref "U11") (pin "18") (pinfunction "MISO_18") (pintype "unspecified"))
    )
    (net (code "108") (name "unconnected-(U11-MOSI-Pad17)") (class "Default")
      (node (ref "U11") (pin "17") (pinfunction "MOSI_17") (pintype "unspecified"))
    )
    (net (code "109") (name "unconnected-(U11-NC-Pad14)") (class "Default")
      (node (ref "U11") (pin "14") (pinfunction "NC_14") (pintype "unspecified"))
    )
    (net (code "110") (name "unconnected-(U11-PCM_CLK-Pad5)") (class "Default")
      (node (ref "U11") (pin "5") (pinfunction "PCM_CLK_5") (pintype "unspecified"))
    )
    (net (code "111") (name "unconnected-(U11-PCM_IN-Pad7)") (class "Default")
      (node (ref "U11") (pin "7") (pinfunction "PCM_IN_7") (pintype "unspecified"))
    )
    (net (code "112") (name "unconnected-(U11-PCM_OUT-Pad6)") (class "Default")
      (node (ref "U11") (pin "6") (pinfunction "PCM_OUT_6") (pintype "unspecified"))
    )
    (net (code "113") (name "unconnected-(U11-PCM_SYNC-Pad8)") (class "Default")
      (node (ref "U11") (pin "8") (pinfunction "PCM_SYNC_8") (pintype "unspecified"))
    )
    (net (code "114") (name "unconnected-(U11-PI00-Pad23)") (class "Default")
      (node (ref "U11") (pin "23") (pinfunction "PI00_23") (pintype "unspecified"))
    )
    (net (code "115") (name "unconnected-(U11-PI01-Pad24)") (class "Default")
      (node (ref "U11") (pin "24") (pinfunction "PI01_24") (pintype "unspecified"))
    )
    (net (code "116") (name "unconnected-(U11-PI02-Pad25)") (class "Default")
      (node (ref "U11") (pin "25") (pinfunction "PI02_25") (pintype "unspecified"))
    )
    (net (code "117") (name "unconnected-(U11-PI03-Pad26)") (class "Default")
      (node (ref "U11") (pin "26") (pinfunction "PI03_26") (pintype "unspecified"))
    )
    (net (code "118") (name "unconnected-(U11-PI04-Pad27)") (class "Default")
      (node (ref "U11") (pin "27") (pinfunction "PI04_27") (pintype "unspecified"))
    )
    (net (code "119") (name "unconnected-(U11-PI05-Pad28)") (class "Default")
      (node (ref "U11") (pin "28") (pinfunction "PI05_28") (pintype "unspecified"))
    )
    (net (code "120") (name "unconnected-(U11-PI06-Pad29)") (class "Default")
      (node (ref "U11") (pin "29") (pinfunction "PI06_29") (pintype "unspecified"))
    )
    (net (code "121") (name "unconnected-(U11-PI07-Pad30)") (class "Default")
      (node (ref "U11") (pin "30") (pinfunction "PI07_30") (pintype "unspecified"))
    )
    (net (code "122") (name "unconnected-(U11-PI010-Pad33)") (class "Default")
      (node (ref "U11") (pin "33") (pinfunction "PI010_33") (pintype "unspecified"))
    )
    (net (code "123") (name "unconnected-(U11-RESET-Pad11)") (class "Default")
      (node (ref "U11") (pin "11") (pinfunction "RESET_11") (pintype "unspecified"))
    )
    (net (code "124") (name "unconnected-(U11-RTS-Pad4)") (class "Default")
      (node (ref "U11") (pin "4") (pinfunction "RTS_4") (pintype "unspecified"))
    )
    (net (code "125") (name "unconnected-(U11-USB_D+-Pad20)") (class "Default")
      (node (ref "U11") (pin "20") (pinfunction "USB_D+_20") (pintype "unspecified"))
    )
    (net (code "126") (name "unconnected-(U11-USB_D--Pad15)") (class "Default")
      (node (ref "U11") (pin "15") (pinfunction "USB_D-_15") (pintype "unspecified"))
    )
    (net (code "127") (name "unconnected-(U12-Pad8)") (class "Default")
      (node (ref "U12") (pin "8") (pinfunction "8_8") (pintype "unspecified"))
    )
    (net (code "128") (name "unconnected-(X1-OE-Pad1)") (class "Default")
      (node (ref "X1") (pin "1") (pinfunction "OE_1") (pintype "unspecified"))
    )
  )
)
